# POWER.net
KiCad netlist of a schematic drawn in Altium Designer
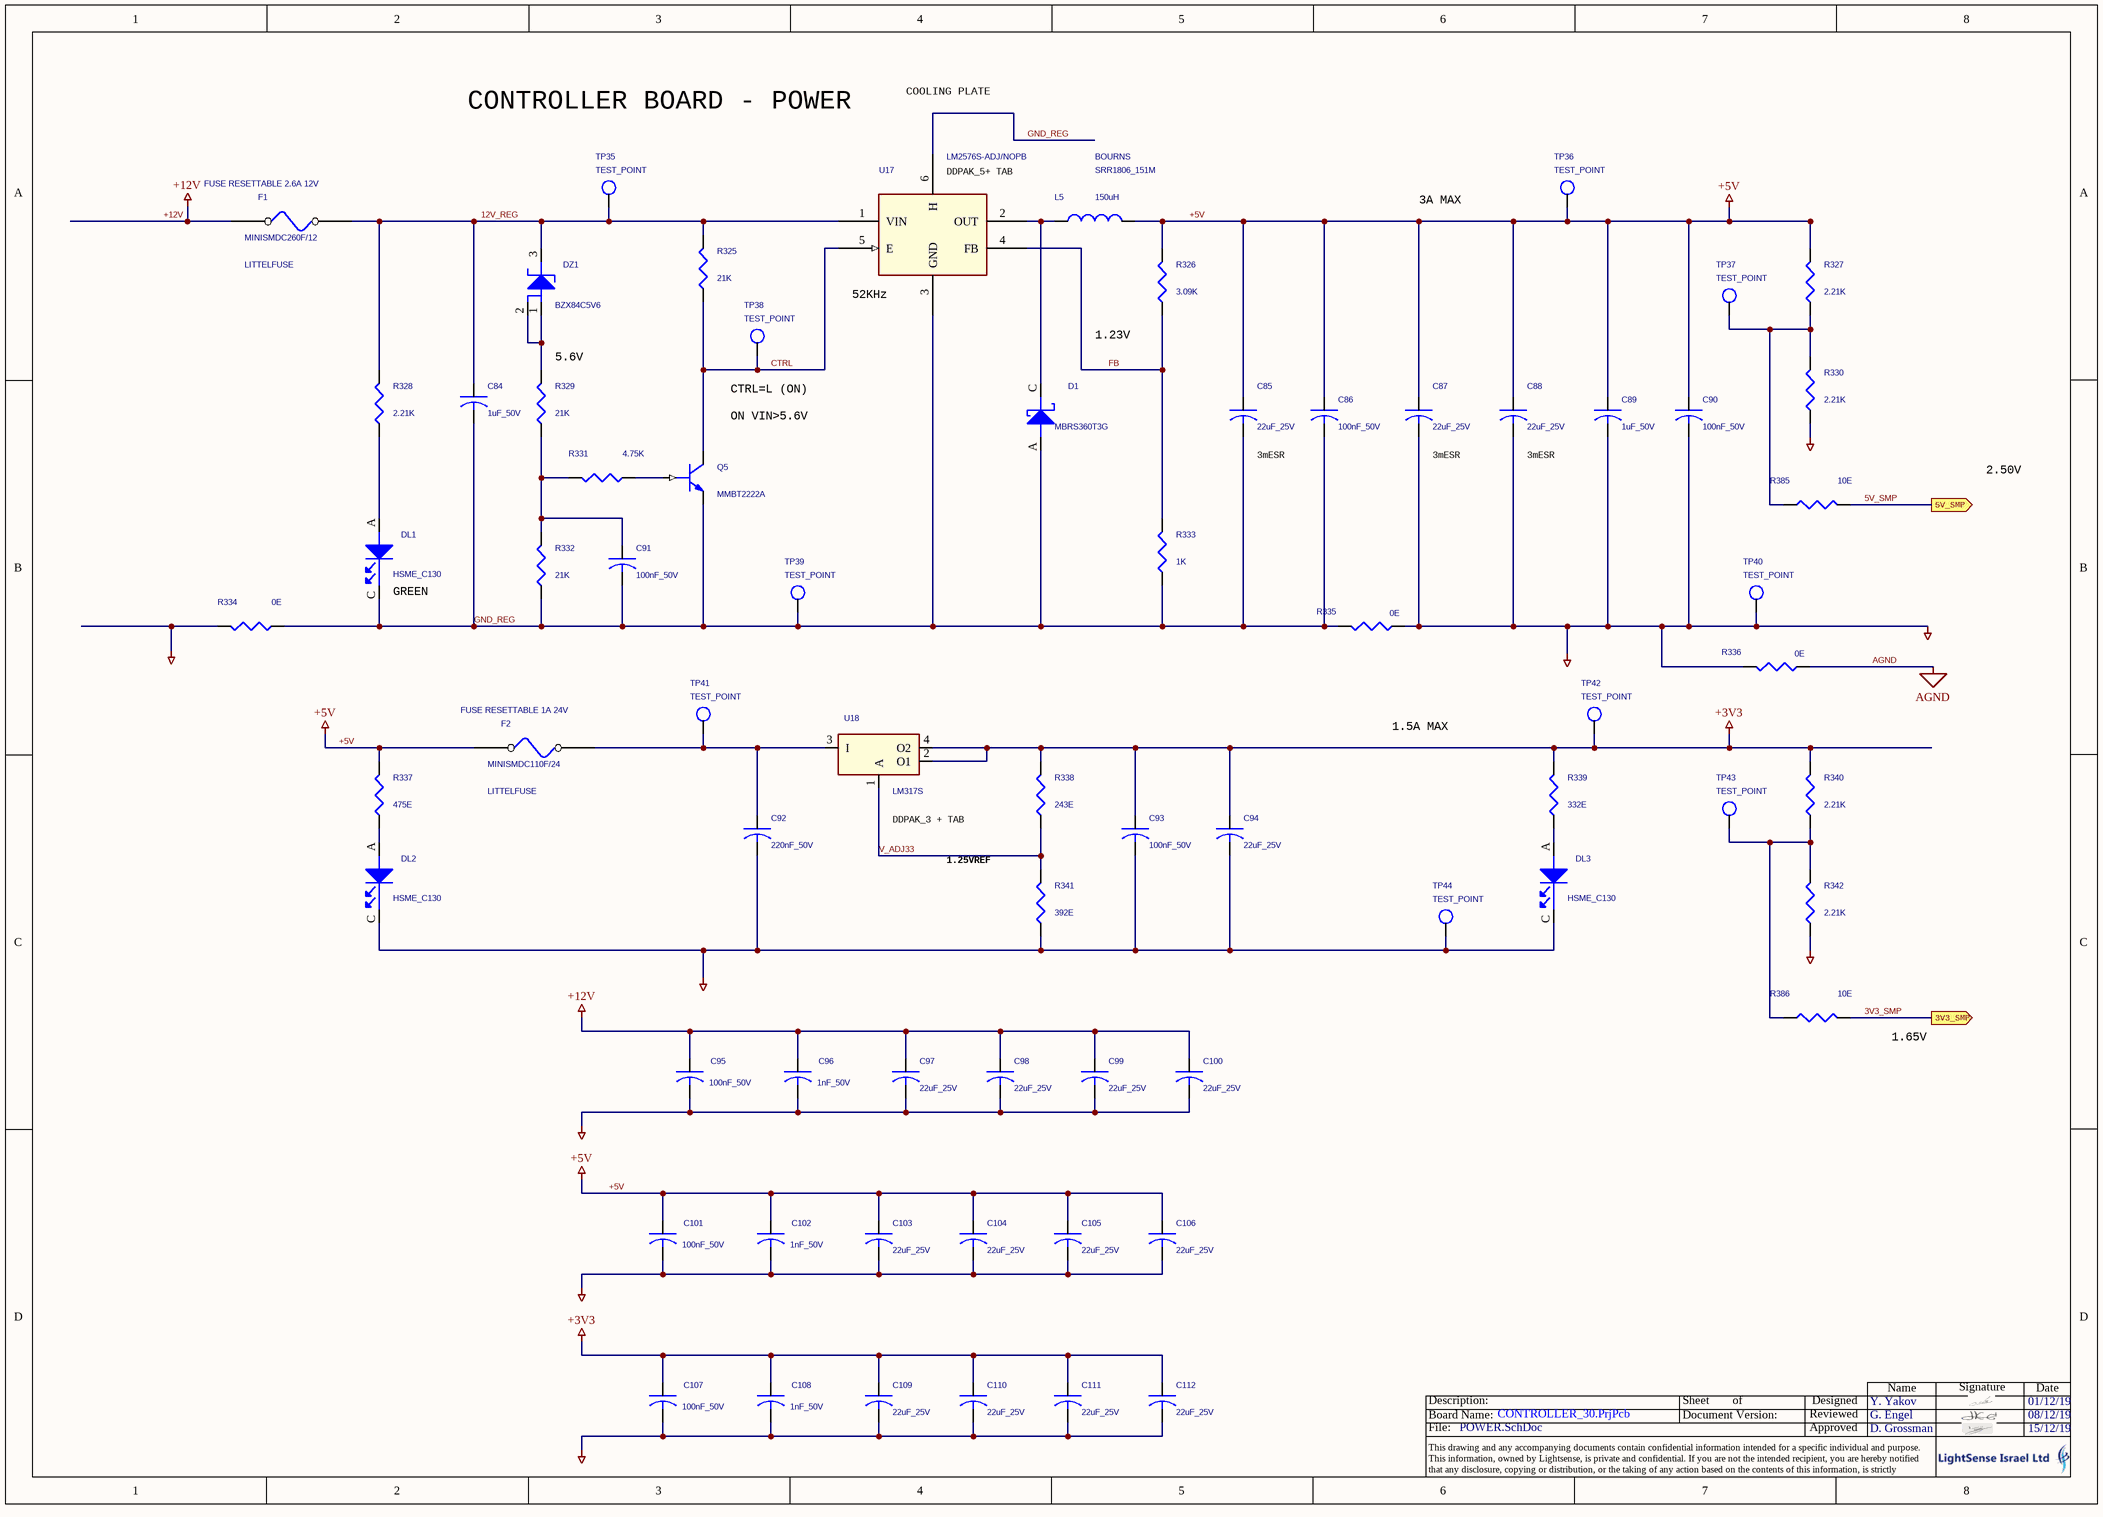
[diagram p0: POWER.SchDoc]

(export (version "E")
  (design (tool "Eeschema 10.0.6"))
  (components
    (comp (ref "C84")
      (value "1uF_50V")
      (footprint "0805")
      (description "a")
      (fields (field (name "MFG") "Murata") (field (name "MNFCTR_PART_NUMBER") "TCJT106M016R0150"))
      (libsource (lib "*") (part "CAP"))
    )
    (comp (ref "C85")
      (value "22uF_25V")
      (footprint "1812")
      (description "a")
      (fields (field (name "MFG") "TDK"))
      (libsource (lib "*") (part "CAP"))
    )
    (comp (ref "C86")
      (value "100nF_50V")
      (footprint "0603")
      (description "CAP_SMT_0603_50V_X7R_10%")
      (fields (field (name "MFG") "KEMET"))
      (libsource (lib "*") (part "C"))
    )
    (comp (ref "C87")
      (value "22uF_25V")
      (footprint "1812")
      (description "a")
      (fields (field (name "MFG") "TDK"))
      (libsource (lib "*") (part "CAP"))
    )
    (comp (ref "C88")
      (value "22uF_25V")
      (footprint "1812")
      (description "a")
      (fields (field (name "MFG") "TDK"))
      (libsource (lib "*") (part "CAP"))
    )
    (comp (ref "C89")
      (value "1uF_50V")
      (footprint "0805")
      (description "a")
      (fields (field (name "MFG") "Murata") (field (name "MNFCTR_PART_NUMBER") "TCJT106M016R0150"))
      (libsource (lib "*") (part "CAP"))
    )
    (comp (ref "C90")
      (value "100nF_50V")
      (footprint "0603")
      (description "CAP_SMT_0603_50V_X7R_10%")
      (fields (field (name "MFG") "KEMET"))
      (libsource (lib "*") (part "C"))
    )
    (comp (ref "C91")
      (value "100nF_50V")
      (footprint "0603")
      (description "CAP_SMT_0603_50V_X7R_10%")
      (fields (field (name "MFG") "KEMET"))
      (libsource (lib "*") (part "C"))
    )
    (comp (ref "C92")
      (value "220nF_50V")
      (footprint "0603")
      (description "CAP_SMT_0603_50V_X7R_10%")
      (fields (field (name "MFG") "TDK"))
      (libsource (lib "*") (part "C"))
    )
    (comp (ref "C93")
      (value "100nF_50V")
      (footprint "0603")
      (description "CAP_SMT_0603_50V_X7R_10%")
      (fields (field (name "MFG") "KEMET"))
      (libsource (lib "*") (part "C"))
    )
    (comp (ref "C94")
      (value "22uF_25V")
      (footprint "1210")
      (description "CAP_SMT_1210_25V_X7R_10%")
      (fields (field (name "MFG") "KEMET"))
      (libsource (lib "*") (part "C"))
    )
    (comp (ref "C95")
      (value "100nF_50V")
      (footprint "0603")
      (description "CAP_SMT_0603_50V_X7R_10%")
      (fields (field (name "MFG") "KEMET"))
      (libsource (lib "*") (part "C"))
    )
    (comp (ref "C96")
      (value "1nF_50V")
      (footprint "0603")
      (description "CAP_SMT_0603_50V_X7R_10%")
      (fields (field (name "MFG") "KEMET"))
      (libsource (lib "*") (part "C"))
    )
    (comp (ref "C97")
      (value "22uF_25V")
      (footprint "1210")
      (description "CAP_SMT_1210_25V_X7R_10%")
      (fields (field (name "MFG") "KEMET"))
      (libsource (lib "*") (part "C"))
    )
    (comp (ref "C98")
      (value "22uF_25V")
      (footprint "1210")
      (description "CAP_SMT_1210_25V_X7R_10%")
      (fields (field (name "MFG") "KEMET"))
      (libsource (lib "*") (part "C"))
    )
    (comp (ref "C99")
      (value "22uF_25V")
      (footprint "1210")
      (description "CAP_SMT_1210_25V_X7R_10%")
      (fields (field (name "MFG") "KEMET"))
      (libsource (lib "*") (part "C"))
    )
    (comp (ref "C100")
      (value "22uF_25V")
      (footprint "1210")
      (description "CAP_SMT_1210_25V_X7R_10%")
      (fields (field (name "MFG") "KEMET"))
      (libsource (lib "*") (part "C"))
    )
    (comp (ref "C101")
      (value "100nF_50V")
      (footprint "0603")
      (description "CAP_SMT_0603_50V_X7R_10%")
      (fields (field (name "MFG") "KEMET"))
      (libsource (lib "*") (part "C"))
    )
    (comp (ref "C102")
      (value "1nF_50V")
      (footprint "0603")
      (description "CAP_SMT_0603_50V_X7R_10%")
      (fields (field (name "MFG") "KEMET"))
      (libsource (lib "*") (part "C"))
    )
    (comp (ref "C103")
      (value "22uF_25V")
      (footprint "1210")
      (description "CAP_SMT_1210_25V_X7R_10%")
      (fields (field (name "MFG") "KEMET"))
      (libsource (lib "*") (part "C"))
    )
    (comp (ref "C104")
      (value "22uF_25V")
      (footprint "1210")
      (description "CAP_SMT_1210_25V_X7R_10%")
      (fields (field (name "MFG") "KEMET"))
      (libsource (lib "*") (part "C"))
    )
    (comp (ref "C105")
      (value "22uF_25V")
      (footprint "1210")
      (description "CAP_SMT_1210_25V_X7R_10%")
      (fields (field (name "MFG") "KEMET"))
      (libsource (lib "*") (part "C"))
    )
    (comp (ref "C106")
      (value "22uF_25V")
      (footprint "1210")
      (description "CAP_SMT_1210_25V_X7R_10%")
      (fields (field (name "MFG") "KEMET"))
      (libsource (lib "*") (part "C"))
    )
    (comp (ref "C107")
      (value "100nF_50V")
      (footprint "0603")
      (description "CAP_SMT_0603_50V_X7R_10%")
      (fields (field (name "MFG") "KEMET"))
      (libsource (lib "*") (part "C"))
    )
    (comp (ref "C108")
      (value "1nF_50V")
      (footprint "0603")
      (description "CAP_SMT_0603_50V_X7R_10%")
      (fields (field (name "MFG") "KEMET"))
      (libsource (lib "*") (part "C"))
    )
    (comp (ref "C109")
      (value "22uF_25V")
      (footprint "1210")
      (description "CAP_SMT_1210_25V_X7R_10%")
      (fields (field (name "MFG") "KEMET"))
      (libsource (lib "*") (part "C"))
    )
    (comp (ref "C110")
      (value "22uF_25V")
      (footprint "1210")
      (description "CAP_SMT_1210_25V_X7R_10%")
      (fields (field (name "MFG") "KEMET"))
      (libsource (lib "*") (part "C"))
    )
    (comp (ref "C111")
      (value "22uF_25V")
      (footprint "1210")
      (description "CAP_SMT_1210_25V_X7R_10%")
      (fields (field (name "MFG") "KEMET"))
      (libsource (lib "*") (part "C"))
    )
    (comp (ref "C112")
      (value "22uF_25V")
      (footprint "1210")
      (description "CAP_SMT_1210_25V_X7R_10%")
      (fields (field (name "MFG") "KEMET"))
      (libsource (lib "*") (part "C"))
    )
    (comp (ref "D1")
      (value "MBRS360T3G")
      (footprint "SMC")
      (fields (field (name "MFG") "ON"))
      (libsource (lib "*") (part "DIODE SCHOTTKY_2"))
    )
    (comp (ref "DL1")
      (value "HSME_C130")
      (footprint "LED_0603")
      (fields (field (name "MFG") "AVAGO"))
      (libsource (lib "*") (part "LED"))
    )
    (comp (ref "DL2")
      (value "HSME_C130")
      (footprint "LED_0603")
      (fields (field (name "MFG") "AVAGO"))
      (libsource (lib "*") (part "LED"))
    )
    (comp (ref "DL3")
      (value "HSME_C130")
      (footprint "LED_0603")
      (fields (field (name "MFG") "AVAGO"))
      (libsource (lib "*") (part "LED"))
    )
    (comp (ref "DZ1")
      (value "BZX84C5V6")
      (footprint "SOT_23")
      (fields (field (name "MFG") "DIODES"))
      (libsource (lib "*") (part "DIODE ZENER S23"))
    )
    (comp (ref "F1")
      (value "FUSE RESETTABLE 2.6A 12V")
      (footprint "F1812")
      (description "FUSE_2.6A_MINISMDC260F/12")
      (fields (field (name "MFG") "LITTELFUSE") (field (name "MFG_PN") "MINISMDC260F/12"))
      (libsource (lib "*") (part "FUSE"))
    )
    (comp (ref "F2")
      (value "FUSE RESETTABLE 1A 24V")
      (footprint "F1812")
      (description "FUSE_2.6A_MINISMDC260F/12")
      (fields (field (name "MFG_PN") "MINISMDC110F/24") (field (name "MFG") "LITTELFUSE"))
      (libsource (lib "*") (part "FUSE"))
    )
    (comp (ref "L5")
      (value "150uH")
      (footprint "SRR1806")
      (fields (field (name "MFG") "BOURNS") (field (name "MFG_PN") "SRR1806_151M"))
      (libsource (lib "*") (part "CHOKE"))
    )
    (comp (ref "Q5")
      (value "MMBT2222A")
      (footprint "SOT_23")
      (fields (field (name "MFG") "ST"))
      (libsource (lib "*") (part "MMBT2222A"))
    )
    (comp (ref "R325")
      (value "21K")
      (footprint "0603")
      (fields (field (name "MFG") "YAGEO"))
      (libsource (lib "*") (part "R_Dup1"))
    )
    (comp (ref "R326")
      (value "3.09K")
      (footprint "0603")
      (fields (field (name "MFG") "YAGEO"))
      (libsource (lib "*") (part "R_Dup1"))
    )
    (comp (ref "R327")
      (value "2.21K")
      (footprint "0603")
      (fields (field (name "MFG") "YAGEO"))
      (libsource (lib "*") (part "R_Dup1"))
    )
    (comp (ref "R328")
      (value "2.21K")
      (footprint "0603")
      (fields (field (name "MFG") "YAGEO"))
      (libsource (lib "*") (part "R_Dup1"))
    )
    (comp (ref "R329")
      (value "21K")
      (footprint "0603")
      (fields (field (name "MFG") "YAGEO"))
      (libsource (lib "*") (part "R_Dup1"))
    )
    (comp (ref "R330")
      (value "2.21K")
      (footprint "0603")
      (fields (field (name "MFG") "YAGEO"))
      (libsource (lib "*") (part "R_Dup1"))
    )
    (comp (ref "R331")
      (value "4.75K")
      (footprint "0603")
      (fields (field (name "MFG") "YAGEO"))
      (libsource (lib "*") (part "R_Dup1"))
    )
    (comp (ref "R332")
      (value "21K")
      (footprint "0603")
      (fields (field (name "MFG") "YAGEO"))
      (libsource (lib "*") (part "R_Dup1"))
    )
    (comp (ref "R333")
      (value "1K")
      (footprint "0603")
      (fields (field (name "MFG") "YAGEO"))
      (libsource (lib "*") (part "R_Dup1"))
    )
    (comp (ref "R334")
      (value "0E")
      (footprint "1812")
      (fields (field (name "MFG") "VISHAY"))
      (libsource (lib "*") (part "R_Dup1"))
    )
    (comp (ref "R335")
      (value "0E")
      (footprint "1812")
      (fields (field (name "MFG") "YAGEO"))
      (libsource (lib "*") (part "R_Dup1"))
    )
    (comp (ref "R336")
      (value "0E")
      (footprint "0805")
      (fields (field (name "MFG") "YAGEO"))
      (libsource (lib "*") (part "R_Dup1"))
    )
    (comp (ref "R337")
      (value "475E")
      (footprint "0603")
      (fields (field (name "MFG") "YAGEO"))
      (libsource (lib "*") (part "R_Dup1"))
    )
    (comp (ref "R338")
      (value "243E")
      (footprint "0603")
      (fields (field (name "MFG") "YAGEO"))
      (libsource (lib "*") (part "R_Dup1"))
    )
    (comp (ref "R339")
      (value "332E")
      (footprint "0603")
      (fields (field (name "MFG") "YAGEO"))
      (libsource (lib "*") (part "R_Dup1"))
    )
    (comp (ref "R340")
      (value "2.21K")
      (footprint "0603")
      (fields (field (name "MFG") "YAGEO"))
      (libsource (lib "*") (part "R_Dup1"))
    )
    (comp (ref "R341")
      (value "392E")
      (footprint "0603")
      (fields (field (name "MFG") "YAGEO"))
      (libsource (lib "*") (part "R_Dup1"))
    )
    (comp (ref "R342")
      (value "2.21K")
      (footprint "0603")
      (fields (field (name "MFG") "YAGEO"))
      (libsource (lib "*") (part "R_Dup1"))
    )
    (comp (ref "R385")
      (value "10E")
      (footprint "0603")
      (fields (field (name "MFG") "YAGEO"))
      (libsource (lib "*") (part "R_Dup1"))
    )
    (comp (ref "R386")
      (value "10E")
      (footprint "0603")
      (fields (field (name "MFG") "YAGEO"))
      (libsource (lib "*") (part "R_Dup1"))
    )
    (comp (ref "TP35")
      (value "TEST_POINT")
      (footprint "TH_1mm")
      (libsource (lib "*") (part "T POINT R_Dup1"))
    )
    (comp (ref "TP36")
      (value "TEST_POINT")
      (footprint "TH_1mm")
      (libsource (lib "*") (part "T POINT R_Dup1"))
    )
    (comp (ref "TP37")
      (value "TEST_POINT")
      (footprint "TH_1mm")
      (libsource (lib "*") (part "T POINT R_Dup1"))
    )
    (comp (ref "TP38")
      (value "TEST_POINT")
      (footprint "TH_1mm")
      (libsource (lib "*") (part "T POINT R_Dup1"))
    )
    (comp (ref "TP39")
      (value "TEST_POINT")
      (footprint "TH_1mm")
      (libsource (lib "*") (part "T POINT R_Dup1"))
    )
    (comp (ref "TP40")
      (value "TEST_POINT")
      (footprint "TH_1mm")
      (libsource (lib "*") (part "T POINT R_Dup1"))
    )
    (comp (ref "TP41")
      (value "TEST_POINT")
      (footprint "TH_1mm")
      (libsource (lib "*") (part "T POINT R_Dup1"))
    )
    (comp (ref "TP42")
      (value "TEST_POINT")
      (footprint "TH_1mm")
      (libsource (lib "*") (part "T POINT R_Dup1"))
    )
    (comp (ref "TP43")
      (value "TEST_POINT")
      (footprint "TH_1mm")
      (libsource (lib "*") (part "T POINT R_Dup1"))
    )
    (comp (ref "TP44")
      (value "TEST_POINT")
      (footprint "TH_1mm")
      (libsource (lib "*") (part "T POINT R_Dup1"))
    )
    (comp (ref "U17")
      (value "LM2576S-ADJ/NOPB")
      (footprint "TO_263_6")
      (fields (field (name "MFG") "TI"))
      (libsource (lib "*") (part "LM2576X/TO263_0"))
    )
    (comp (ref "U18")
      (value "LM317S")
      (footprint "TO_263_4")
      (fields (field (name "MFG") "NATIONAL"))
      (libsource (lib "*") (part "LM317EMP"))
    )
  )
  (nets
    (net (code "1") (name "+3V3") (class "Default")
      (node (ref "C107") (pin "1") (pinfunction "1_1") (pintype "passive"))
      (node (ref "C108") (pin "1") (pinfunction "1_1") (pintype "passive"))
      (node (ref "C109") (pin "1") (pinfunction "1_1") (pintype "passive"))
      (node (ref "C110") (pin "1") (pinfunction "1_1") (pintype "passive"))
      (node (ref "C111") (pin "1") (pinfunction "1_1") (pintype "passive"))
      (node (ref "C112") (pin "1") (pinfunction "1_1") (pintype "passive"))
      (node (ref "C93") (pin "1") (pinfunction "1_1") (pintype "passive"))
      (node (ref "C94") (pin "1") (pinfunction "1_1") (pintype "passive"))
      (node (ref "R338") (pin "2") (pinfunction "2_2") (pintype "passive"))
      (node (ref "R339") (pin "2") (pinfunction "2_2") (pintype "passive"))
      (node (ref "R340") (pin "2") (pinfunction "2_2") (pintype "passive"))
      (node (ref "TP42") (pin "1") (pinfunction "TP_1") (pintype "passive"))
      (node (ref "U18") (pin "2") (pinfunction "O1_2") (pintype "passive"))
      (node (ref "U18") (pin "4") (pinfunction "O2_4") (pintype "passive"))
    )
    (net (code "2") (name "+5V") (class "Default")
      (node (ref "C101") (pin "1") (pinfunction "1_1") (pintype "passive"))
      (node (ref "C102") (pin "1") (pinfunction "1_1") (pintype "passive"))
      (node (ref "C103") (pin "1") (pinfunction "1_1") (pintype "passive"))
      (node (ref "C104") (pin "1") (pinfunction "1_1") (pintype "passive"))
      (node (ref "C105") (pin "1") (pinfunction "1_1") (pintype "passive"))
      (node (ref "C106") (pin "1") (pinfunction "1_1") (pintype "passive"))
      (node (ref "C85") (pin "1") (pinfunction "1_1") (pintype "passive"))
      (node (ref "C86") (pin "1") (pinfunction "1_1") (pintype "passive"))
      (node (ref "C87") (pin "1") (pinfunction "1_1") (pintype "passive"))
      (node (ref "C88") (pin "1") (pinfunction "1_1") (pintype "passive"))
      (node (ref "C89") (pin "1") (pinfunction "1_1") (pintype "passive"))
      (node (ref "C90") (pin "1") (pinfunction "1_1") (pintype "passive"))
      (node (ref "F2") (pin "1") (pinfunction "1_1") (pintype "passive"))
      (node (ref "L5") (pin "2") (pinfunction "2_2") (pintype "passive"))
      (node (ref "R326") (pin "2") (pinfunction "2_2") (pintype "passive"))
      (node (ref "R327") (pin "2") (pinfunction "2_2") (pintype "passive"))
      (node (ref "R337") (pin "2") (pinfunction "2_2") (pintype "passive"))
      (node (ref "TP36") (pin "1") (pinfunction "TP_1") (pintype "passive"))
    )
    (net (code "3") (name "+12V") (class "Default")
      (node (ref "C100") (pin "1") (pinfunction "1_1") (pintype "passive"))
      (node (ref "C95") (pin "1") (pinfunction "1_1") (pintype "passive"))
      (node (ref "C96") (pin "1") (pinfunction "1_1") (pintype "passive"))
      (node (ref "C97") (pin "1") (pinfunction "1_1") (pintype "passive"))
      (node (ref "C98") (pin "1") (pinfunction "1_1") (pintype "passive"))
      (node (ref "C99") (pin "1") (pinfunction "1_1") (pintype "passive"))
      (node (ref "F1") (pin "1") (pinfunction "1_1") (pintype "passive"))
    )
    (net (code "4") (name "/3V3_SMP") (class "Default")
      (node (ref "R386") (pin "2") (pinfunction "2_2") (pintype "passive"))
    )
    (net (code "5") (name "/5V_SMP") (class "Default")
      (node (ref "R385") (pin "2") (pinfunction "2_2") (pintype "passive"))
    )
    (net (code "6") (name "/12V_REG") (class "Default")
      (node (ref "C84") (pin "1") (pinfunction "1_1") (pintype "passive"))
      (node (ref "DZ1") (pin "3") (pinfunction "CATHODE_3") (pintype "passive"))
      (node (ref "F1") (pin "2") (pinfunction "2_2") (pintype "passive"))
      (node (ref "R325") (pin "2") (pinfunction "2_2") (pintype "passive"))
      (node (ref "R328") (pin "2") (pinfunction "2_2") (pintype "passive"))
      (node (ref "TP35") (pin "1") (pinfunction "TP_1") (pintype "passive"))
      (node (ref "U17") (pin "1") (pinfunction "VIN_1") (pintype "passive"))
    )
    (net (code "7") (name "/CTRL") (class "Default")
      (node (ref "Q5") (pin "3") (pinfunction "COLLECTOR_3") (pintype "passive"))
      (node (ref "R325") (pin "1") (pinfunction "1_1") (pintype "passive"))
      (node (ref "TP38") (pin "1") (pinfunction "TP_1") (pintype "passive"))
      (node (ref "U17") (pin "5") (pinfunction "E_5") (pintype "input"))
    )
    (net (code "8") (name "/FB") (class "Default")
      (node (ref "R326") (pin "1") (pinfunction "1_1") (pintype "passive"))
      (node (ref "R333") (pin "2") (pinfunction "2_2") (pintype "passive"))
      (node (ref "U17") (pin "4") (pinfunction "FB_4") (pintype "passive"))
    )
    (net (code "9") (name "/GND_REG") (class "Default")
      (node (ref "C84") (pin "2") (pinfunction "2_2") (pintype "passive"))
      (node (ref "C85") (pin "2") (pinfunction "2_2") (pintype "passive"))
      (node (ref "C86") (pin "2") (pinfunction "2_2") (pintype "passive"))
      (node (ref "C91") (pin "2") (pinfunction "2_2") (pintype "passive"))
      (node (ref "D1") (pin "A") (pinfunction "A_A") (pintype "passive"))
      (node (ref "DL1") (pin "C") (pinfunction "CATHODE_C") (pintype "passive"))
      (node (ref "Q5") (pin "2") (pinfunction "EMITTER_2") (pintype "passive"))
      (node (ref "R332") (pin "1") (pinfunction "1_1") (pintype "passive"))
      (node (ref "R333") (pin "1") (pinfunction "1_1") (pintype "passive"))
      (node (ref "R334") (pin "1") (pinfunction "1_1") (pintype "passive"))
      (node (ref "R335") (pin "2") (pinfunction "2_2") (pintype "passive"))
      (node (ref "TP39") (pin "1") (pinfunction "TP_1") (pintype "passive"))
      (node (ref "U17") (pin "3") (pinfunction "GND_3") (pintype "passive"))
      (node (ref "U17") (pin "6") (pinfunction "H_6") (pintype "passive"))
    )
    (net (code "10") (name "/V_ADJ33") (class "Default")
      (node (ref "R338") (pin "1") (pinfunction "1_1") (pintype "passive"))
      (node (ref "R341") (pin "2") (pinfunction "2_2") (pintype "passive"))
      (node (ref "U18") (pin "1") (pinfunction "A_1") (pintype "passive"))
    )
    (net (code "11") (name "AGND") (class "Default")
      (node (ref "R336") (pin "1") (pinfunction "1_1") (pintype "passive"))
    )
    (net (code "12") (name "GND_CPU") (class "Default")
      (node (ref "C101") (pin "2") (pinfunction "2_2") (pintype "passive"))
      (node (ref "C102") (pin "2") (pinfunction "2_2") (pintype "passive"))
      (node (ref "C103") (pin "2") (pinfunction "2_2") (pintype "passive"))
      (node (ref "C104") (pin "2") (pinfunction "2_2") (pintype "passive"))
      (node (ref "C105") (pin "2") (pinfunction "2_2") (pintype "passive"))
      (node (ref "C106") (pin "2") (pinfunction "2_2") (pintype "passive"))
      (node (ref "C107") (pin "2") (pinfunction "2_2") (pintype "passive"))
      (node (ref "C108") (pin "2") (pinfunction "2_2") (pintype "passive"))
      (node (ref "C109") (pin "2") (pinfunction "2_2") (pintype "passive"))
      (node (ref "C110") (pin "2") (pinfunction "2_2") (pintype "passive"))
      (node (ref "C111") (pin "2") (pinfunction "2_2") (pintype "passive"))
      (node (ref "C112") (pin "2") (pinfunction "2_2") (pintype "passive"))
      (node (ref "C87") (pin "2") (pinfunction "2_2") (pintype "passive"))
      (node (ref "C88") (pin "2") (pinfunction "2_2") (pintype "passive"))
      (node (ref "C89") (pin "2") (pinfunction "2_2") (pintype "passive"))
      (node (ref "C90") (pin "2") (pinfunction "2_2") (pintype "passive"))
      (node (ref "C92") (pin "2") (pinfunction "2_2") (pintype "passive"))
      (node (ref "C93") (pin "2") (pinfunction "2_2") (pintype "passive"))
      (node (ref "C94") (pin "2") (pinfunction "2_2") (pintype "passive"))
      (node (ref "DL2") (pin "C") (pinfunction "CATHODE_C") (pintype "passive"))
      (node (ref "DL3") (pin "C") (pinfunction "CATHODE_C") (pintype "passive"))
      (node (ref "R330") (pin "1") (pinfunction "1_1") (pintype "passive"))
      (node (ref "R335") (pin "1") (pinfunction "1_1") (pintype "passive"))
      (node (ref "R336") (pin "2") (pinfunction "2_2") (pintype "passive"))
      (node (ref "R341") (pin "1") (pinfunction "1_1") (pintype "passive"))
      (node (ref "R342") (pin "1") (pinfunction "1_1") (pintype "passive"))
      (node (ref "TP40") (pin "1") (pinfunction "TP_1") (pintype "passive"))
      (node (ref "TP44") (pin "1") (pinfunction "TP_1") (pintype "passive"))
    )
    (net (code "13") (name "GND_M") (class "Default")
      (node (ref "C100") (pin "2") (pinfunction "2_2") (pintype "passive"))
      (node (ref "C95") (pin "2") (pinfunction "2_2") (pintype "passive"))
      (node (ref "C96") (pin "2") (pinfunction "2_2") (pintype "passive"))
      (node (ref "C97") (pin "2") (pinfunction "2_2") (pintype "passive"))
      (node (ref "C98") (pin "2") (pinfunction "2_2") (pintype "passive"))
      (node (ref "C99") (pin "2") (pinfunction "2_2") (pintype "passive"))
      (node (ref "R334") (pin "2") (pinfunction "2_2") (pintype "passive"))
    )
    (net (code "14") (name "Net-(C91-Pad1)") (class "Default")
      (node (ref "C91") (pin "1") (pinfunction "1_1") (pintype "passive"))
      (node (ref "R329") (pin "1") (pinfunction "1_1") (pintype "passive"))
      (node (ref "R331") (pin "2") (pinfunction "2_2") (pintype "passive"))
      (node (ref "R332") (pin "2") (pinfunction "2_2") (pintype "passive"))
    )
    (net (code "15") (name "Net-(DL1-ANODE)") (class "Default")
      (node (ref "DL1") (pin "A") (pinfunction "ANODE_A") (pintype "passive"))
      (node (ref "R328") (pin "1") (pinfunction "1_1") (pintype "passive"))
    )
    (net (code "16") (name "Net-(DL2-ANODE)") (class "Default")
      (node (ref "DL2") (pin "A") (pinfunction "ANODE_A") (pintype "passive"))
      (node (ref "R337") (pin "1") (pinfunction "1_1") (pintype "passive"))
    )
    (net (code "17") (name "Net-(DL3-ANODE)") (class "Default")
      (node (ref "DL3") (pin "A") (pinfunction "ANODE_A") (pintype "passive"))
      (node (ref "R339") (pin "1") (pinfunction "1_1") (pintype "passive"))
    )
    (net (code "18") (name "Net-(DZ1-ANODE_1)") (class "Default")
      (node (ref "DZ1") (pin "1") (pinfunction "ANODE_1_1") (pintype "passive"))
      (node (ref "DZ1") (pin "2") (pinfunction "Anode_2_2") (pintype "passive"))
      (node (ref "R329") (pin "2") (pinfunction "2_2") (pintype "passive"))
    )
    (net (code "19") (name "Net-(Q5-BASE)") (class "Default")
      (node (ref "Q5") (pin "1") (pinfunction "BASE_1") (pintype "input"))
      (node (ref "R331") (pin "1") (pinfunction "1_1") (pintype "passive"))
    )
    (net (code "20") (name "Net-(TP37-TP)") (class "Default")
      (node (ref "R327") (pin "1") (pinfunction "1_1") (pintype "passive"))
      (node (ref "R330") (pin "2") (pinfunction "2_2") (pintype "passive"))
      (node (ref "R385") (pin "1") (pinfunction "1_1") (pintype "passive"))
      (node (ref "TP37") (pin "1") (pinfunction "TP_1") (pintype "passive"))
    )
    (net (code "21") (name "Net-(TP41-TP)") (class "Default")
      (node (ref "C92") (pin "1") (pinfunction "1_1") (pintype "passive"))
      (node (ref "F2") (pin "2") (pinfunction "2_2") (pintype "passive"))
      (node (ref "TP41") (pin "1") (pinfunction "TP_1") (pintype "passive"))
      (node (ref "U18") (pin "3") (pinfunction "I_3") (pintype "passive"))
    )
    (net (code "22") (name "Net-(TP43-TP)") (class "Default")
      (node (ref "R340") (pin "1") (pinfunction "1_1") (pintype "passive"))
      (node (ref "R342") (pin "2") (pinfunction "2_2") (pintype "passive"))
      (node (ref "R386") (pin "1") (pinfunction "1_1") (pintype "passive"))
      (node (ref "TP43") (pin "1") (pinfunction "TP_1") (pintype "passive"))
    )
    (net (code "23") (name "Net-(U17-OUT)") (class "Default")
      (node (ref "D1") (pin "C") (pinfunction "C_C") (pintype "passive"))
      (node (ref "L5") (pin "1") (pinfunction "1_1") (pintype "passive"))
      (node (ref "U17") (pin "2") (pinfunction "OUT_2") (pintype "passive"))
    )
  )
)
